# Schematic.net
KiCad netlist of a schematic drawn in EAGLE
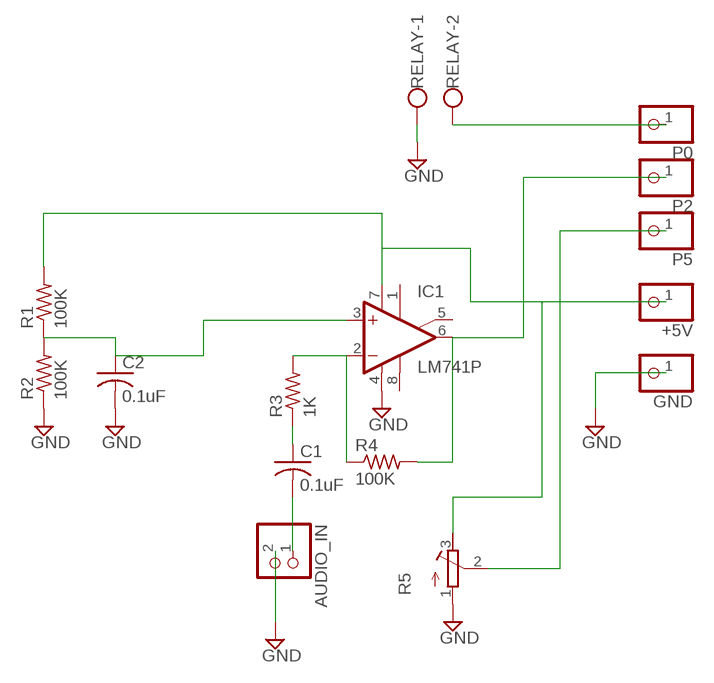
[diagram p0: schematic, sheet 1]

(export (version "E")
  (design (tool "Eeschema 10.0.6"))
  (components
    (comp (ref "+5V")
      (value "PINHD-1X1")
      (footprint "eagle-import:1X01")
      (libsource (lib "eagle-import") (part "PINHD-1X1"))
    )
    (comp (ref "AUDIO_IN")
      (value "PINHD-1X2")
      (footprint "eagle-import:1X02")
      (libsource (lib "eagle-import") (part "PINHD-1X2"))
    )
    (comp (ref "C1")
      (value "0.1uF")
      (footprint "eagle-import:C025-024X044")
      (libsource (lib "eagle-import") (part "C-US025-024X044"))
    )
    (comp (ref "C2")
      (value "0.1uF")
      (footprint "eagle-import:C025-024X044")
      (libsource (lib "eagle-import") (part "C-US025-024X044"))
    )
    (comp (ref "GND")
      (value "PINHD-1X1")
      (footprint "eagle-import:1X01")
      (libsource (lib "eagle-import") (part "PINHD-1X1"))
    )
    (comp (ref "IC1")
      (value "LM741P")
      (footprint "eagle-import:DIL08")
      (libsource (lib "eagle-import") (part "741PLM"))
    )
    (comp (ref "P0")
      (value "PINHD-1X1")
      (footprint "eagle-import:1X01")
      (libsource (lib "eagle-import") (part "PINHD-1X1"))
    )
    (comp (ref "P2")
      (value "PINHD-1X1")
      (footprint "eagle-import:1X01")
      (libsource (lib "eagle-import") (part "PINHD-1X1"))
    )
    (comp (ref "P5")
      (value "PINHD-1X1")
      (footprint "eagle-import:1X01")
      (libsource (lib "eagle-import") (part "PINHD-1X1"))
    )
    (comp (ref "R1")
      (value "100K")
      (footprint "eagle-import:0207_2V")
      (libsource (lib "eagle-import") (part "R-US_0207/2V"))
    )
    (comp (ref "R2")
      (value "100K")
      (footprint "eagle-import:0207_2V")
      (libsource (lib "eagle-import") (part "R-US_0207/2V"))
    )
    (comp (ref "R3")
      (value "1K")
      (footprint "eagle-import:0207_2V")
      (libsource (lib "eagle-import") (part "R-US_0207/2V"))
    )
    (comp (ref "R4")
      (value "100K")
      (footprint "eagle-import:0207_2V")
      (libsource (lib "eagle-import") (part "R-US_0207/2V"))
    )
    (comp (ref "R5")
      (value "R-TRIMM64W")
      (footprint "eagle-import:RTRIM64W")
      (libsource (lib "eagle-import") (part "R-TRIMM64W"))
    )
    (comp (ref "RELAY")
      (value "W237-102")
      (footprint "eagle-import:W237-102")
      (fields (field (name "MPN") "237-102"))
      (libsource (lib "eagle-import") (part "W237-102"))
    )
  )
  (nets
    (net (code "1") (name "GND") (class "Default")
      (node (ref "AUDIO_IN") (pin "2") (pinfunction "2_2") (pintype "passive"))
      (node (ref "C2") (pin "2") (pinfunction "2_2") (pintype "passive"))
      (node (ref "GND") (pin "1") (pinfunction "1_1") (pintype "passive"))
      (node (ref "IC1") (pin "4") (pinfunction "V-_4") (pintype "power_in"))
      (node (ref "R2") (pin "1") (pinfunction "1_1") (pintype "passive"))
      (node (ref "R5") (pin "1") (pinfunction "E_1") (pintype "passive"))
      (node (ref "RELAY") (pin "1") (pinfunction "KL_1") (pintype "passive"))
    )
    (net (code "2") (name "Net-(AUDIO_IN-Pad1)") (class "Default")
      (node (ref "AUDIO_IN") (pin "1") (pinfunction "1_1") (pintype "passive"))
      (node (ref "C1") (pin "2") (pinfunction "2_2") (pintype "passive"))
    )
    (net (code "3") (name "Net-(C1-Pad1)") (class "Default")
      (node (ref "C1") (pin "1") (pinfunction "1_1") (pintype "passive"))
      (node (ref "R3") (pin "1") (pinfunction "1_1") (pintype "passive"))
    )
    (net (code "4") (name "Net-(IC1-+IN)") (class "Default")
      (node (ref "C2") (pin "1") (pinfunction "1_1") (pintype "passive"))
      (node (ref "IC1") (pin "3") (pinfunction "+IN_3") (pintype "input"))
      (node (ref "R1") (pin "1") (pinfunction "1_1") (pintype "passive"))
      (node (ref "R2") (pin "2") (pinfunction "2_2") (pintype "passive"))
    )
    (net (code "5") (name "Net-(IC1--IN)") (class "Default")
      (node (ref "IC1") (pin "2") (pinfunction "-IN_2") (pintype "input"))
      (node (ref "R3") (pin "2") (pinfunction "2_2") (pintype "passive"))
      (node (ref "R4") (pin "1") (pinfunction "1_1") (pintype "passive"))
    )
    (net (code "6") (name "Net-(IC1-OUT)") (class "Default")
      (node (ref "IC1") (pin "6") (pinfunction "OUT_6") (pintype "output"))
      (node (ref "P2") (pin "1") (pinfunction "1_1") (pintype "passive"))
      (node (ref "R4") (pin "2") (pinfunction "2_2") (pintype "passive"))
    )
    (net (code "7") (name "Net-(IC1-V+)") (class "Default")
      (node (ref "+5V") (pin "1") (pinfunction "1_1") (pintype "passive"))
      (node (ref "IC1") (pin "7") (pinfunction "V+_7") (pintype "power_in"))
      (node (ref "R1") (pin "2") (pinfunction "2_2") (pintype "passive"))
      (node (ref "R5") (pin "3") (pinfunction "A_3") (pintype "passive"))
    )
    (net (code "8") (name "Net-(R5-S)") (class "Default")
      (node (ref "P5") (pin "1") (pinfunction "1_1") (pintype "passive"))
      (node (ref "R5") (pin "2") (pinfunction "S_2") (pintype "passive"))
    )
    (net (code "9") (name "Net-(RELAYB-KL)") (class "Default")
      (node (ref "P0") (pin "1") (pinfunction "1_1") (pintype "passive"))
      (node (ref "RELAY") (pin "2") (pinfunction "KL_2") (pintype "passive"))
    )
    (net (code "10") (name "unconnected-(IC1-ON1-Pad1)") (class "Default")
      (node (ref "IC1") (pin "1") (pinfunction "ON1_1") (pintype "passive"))
    )
    (net (code "11") (name "unconnected-(IC1-ON2-Pad5)") (class "Default")
      (node (ref "IC1") (pin "5") (pinfunction "ON2_5") (pintype "passive"))
    )
    (net (code "12") (name "unconnected-(IC1-OPT-Pad8)") (class "Default")
      (node (ref "IC1") (pin "8") (pinfunction "OPT_8") (pintype "passive"))
    )
  )
)
